# switch-matrix.net
KiCad netlist of a schematic drawn in EAGLE
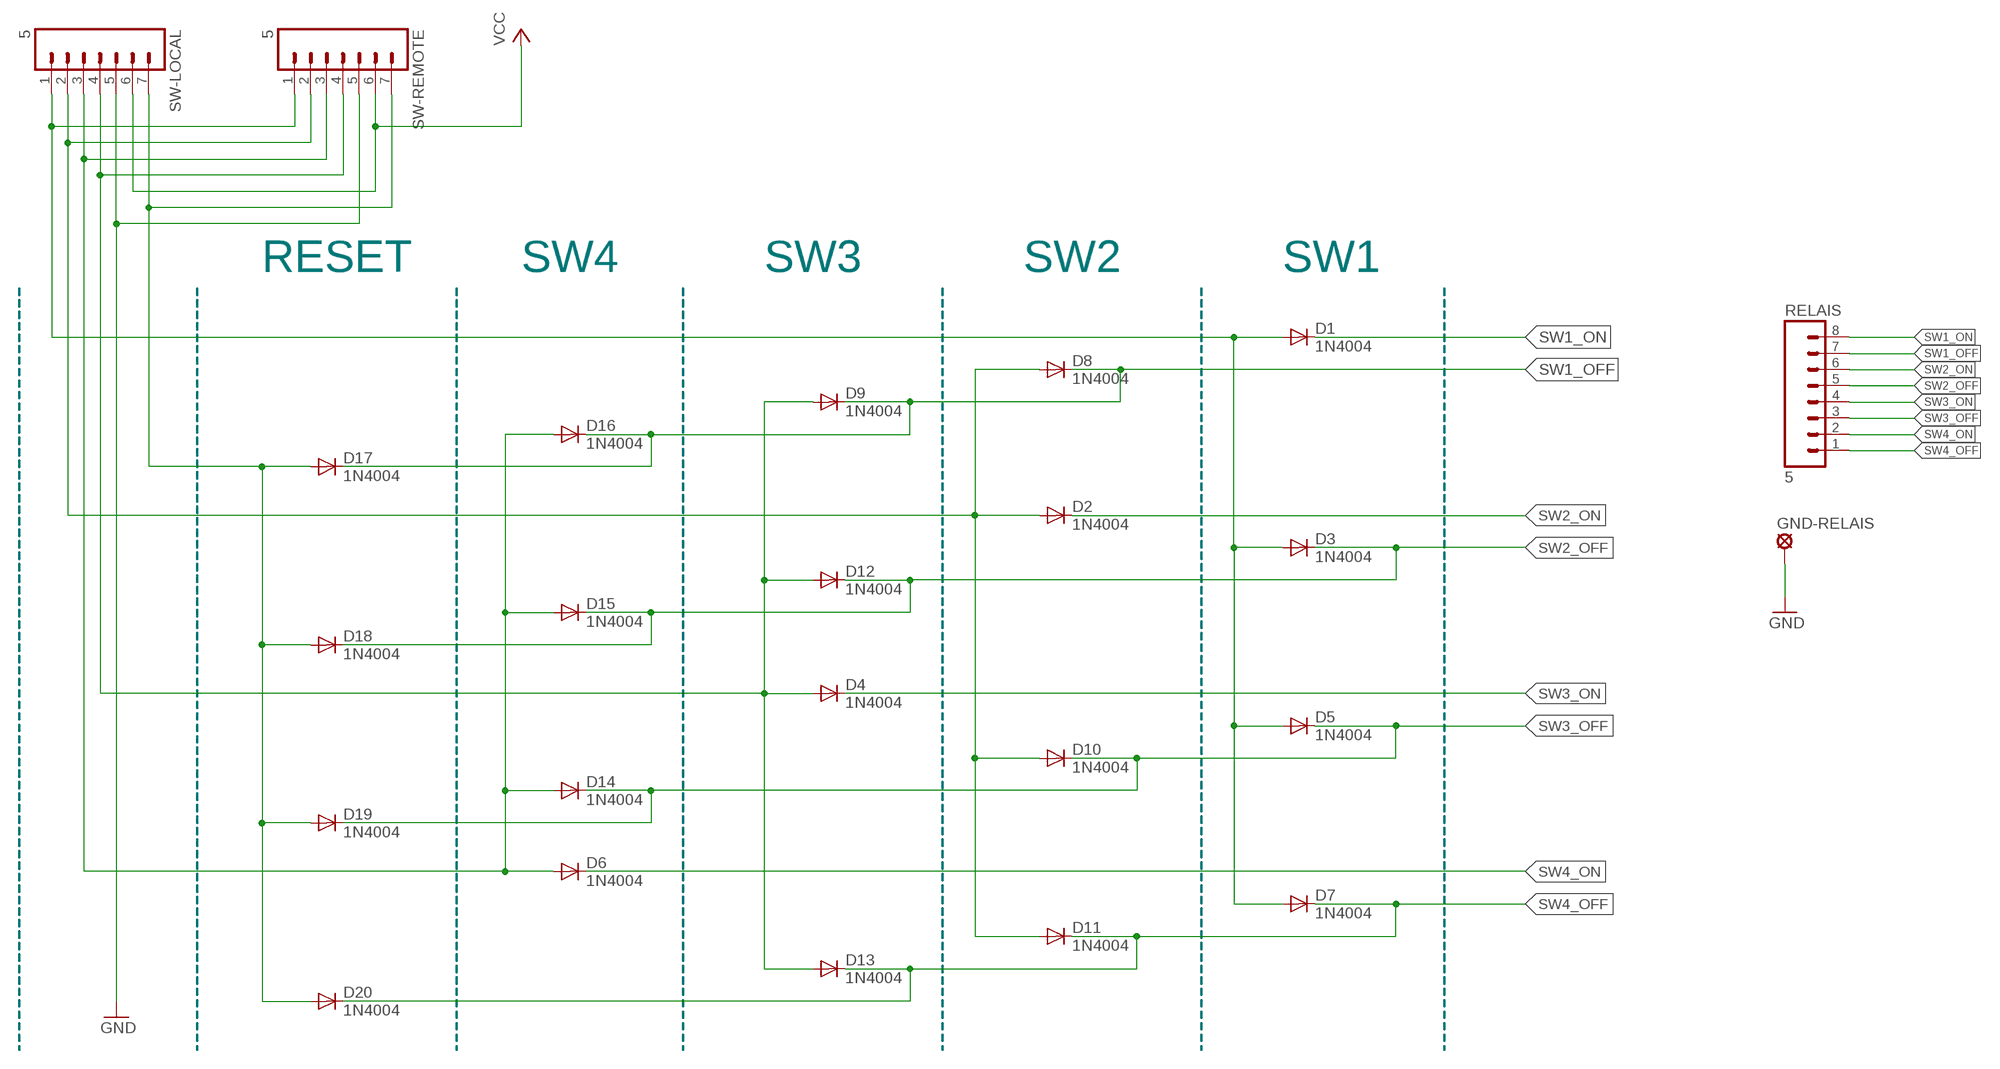
[diagram p0: schematic, sheet 1]

(export (version "E")
  (design (tool "Eeschema 10.0.6"))
  (components
    (comp (ref "D1")
      (value "1N4004")
      (footprint "eagle-import:DO41-10")
      (libsource (lib "eagle-import") (part "1N4004"))
    )
    (comp (ref "D2")
      (value "1N4004")
      (footprint "eagle-import:DO41-10")
      (libsource (lib "eagle-import") (part "1N4004"))
    )
    (comp (ref "D3")
      (value "1N4004")
      (footprint "eagle-import:DO41-10")
      (libsource (lib "eagle-import") (part "1N4004"))
    )
    (comp (ref "D4")
      (value "1N4004")
      (footprint "eagle-import:DO41-10")
      (libsource (lib "eagle-import") (part "1N4004"))
    )
    (comp (ref "D5")
      (value "1N4004")
      (footprint "eagle-import:DO41-10")
      (libsource (lib "eagle-import") (part "1N4004"))
    )
    (comp (ref "D6")
      (value "1N4004")
      (footprint "eagle-import:DO41-10")
      (libsource (lib "eagle-import") (part "1N4004"))
    )
    (comp (ref "D7")
      (value "1N4004")
      (footprint "eagle-import:DO41-10")
      (libsource (lib "eagle-import") (part "1N4004"))
    )
    (comp (ref "D8")
      (value "1N4004")
      (footprint "eagle-import:DO41-10")
      (libsource (lib "eagle-import") (part "1N4004"))
    )
    (comp (ref "D9")
      (value "1N4004")
      (footprint "eagle-import:DO41-10")
      (libsource (lib "eagle-import") (part "1N4004"))
    )
    (comp (ref "D10")
      (value "1N4004")
      (footprint "eagle-import:DO41-10")
      (libsource (lib "eagle-import") (part "1N4004"))
    )
    (comp (ref "D11")
      (value "1N4004")
      (footprint "eagle-import:DO41-10")
      (libsource (lib "eagle-import") (part "1N4004"))
    )
    (comp (ref "D12")
      (value "1N4004")
      (footprint "eagle-import:DO41-10")
      (libsource (lib "eagle-import") (part "1N4004"))
    )
    (comp (ref "D13")
      (value "1N4004")
      (footprint "eagle-import:DO41-10")
      (libsource (lib "eagle-import") (part "1N4004"))
    )
    (comp (ref "D14")
      (value "1N4004")
      (footprint "eagle-import:DO41-10")
      (libsource (lib "eagle-import") (part "1N4004"))
    )
    (comp (ref "D15")
      (value "1N4004")
      (footprint "eagle-import:DO41-10")
      (libsource (lib "eagle-import") (part "1N4004"))
    )
    (comp (ref "D16")
      (value "1N4004")
      (footprint "eagle-import:DO41-10")
      (libsource (lib "eagle-import") (part "1N4004"))
    )
    (comp (ref "D17")
      (value "1N4004")
      (footprint "eagle-import:DO41-10")
      (libsource (lib "eagle-import") (part "1N4004"))
    )
    (comp (ref "D18")
      (value "1N4004")
      (footprint "eagle-import:DO41-10")
      (libsource (lib "eagle-import") (part "1N4004"))
    )
    (comp (ref "D19")
      (value "1N4004")
      (footprint "eagle-import:DO41-10")
      (libsource (lib "eagle-import") (part "1N4004"))
    )
    (comp (ref "D20")
      (value "1N4004")
      (footprint "eagle-import:DO41-10")
      (libsource (lib "eagle-import") (part "1N4004"))
    )
    (comp (ref "GND-RELAIS")
      (value "LSP10")
      (footprint "eagle-import:LSP10")
      (libsource (lib "eagle-import") (part "LSP10"))
    )
    (comp (ref "RELAIS")
      (value "5")
      (footprint "eagle-import:08PA")
      (libsource (lib "eagle-import") (part "MA08"))
    )
    (comp (ref "SW-LOCAL")
      (value "5")
      (footprint "eagle-import:07PA")
      (libsource (lib "eagle-import") (part "MA07"))
    )
    (comp (ref "SW-REMOTE")
      (value "5")
      (footprint "eagle-import:07PA")
      (libsource (lib "eagle-import") (part "MA07"))
    )
  )
  (nets
    (net (code "1") (name "GND") (class "Default")
      (node (ref "GND-RELAIS") (pin "MP") (pinfunction "MP_MP") (pintype "passive"))
      (node (ref "SW-LOCAL") (pin "5") (pinfunction "5_5") (pintype "passive"))
      (node (ref "SW-REMOTE") (pin "5") (pinfunction "5_5") (pintype "passive"))
    )
    (net (code "2") (name "Net-(D1-PadA)") (class "Default")
      (node (ref "D1") (pin "A") (pinfunction "A_A") (pintype "passive"))
      (node (ref "D3") (pin "A") (pinfunction "A_A") (pintype "passive"))
      (node (ref "D5") (pin "A") (pinfunction "A_A") (pintype "passive"))
      (node (ref "D7") (pin "A") (pinfunction "A_A") (pintype "passive"))
      (node (ref "SW-LOCAL") (pin "1") (pinfunction "1_1") (pintype "passive"))
      (node (ref "SW-REMOTE") (pin "1") (pinfunction "1_1") (pintype "passive"))
    )
    (net (code "3") (name "Net-(D10-PadA)") (class "Default")
      (node (ref "D10") (pin "A") (pinfunction "A_A") (pintype "passive"))
      (node (ref "D11") (pin "A") (pinfunction "A_A") (pintype "passive"))
      (node (ref "D2") (pin "A") (pinfunction "A_A") (pintype "passive"))
      (node (ref "D8") (pin "A") (pinfunction "A_A") (pintype "passive"))
      (node (ref "SW-LOCAL") (pin "2") (pinfunction "2_2") (pintype "passive"))
      (node (ref "SW-REMOTE") (pin "2") (pinfunction "2_2") (pintype "passive"))
    )
    (net (code "4") (name "Net-(D12-PadA)") (class "Default")
      (node (ref "D12") (pin "A") (pinfunction "A_A") (pintype "passive"))
      (node (ref "D13") (pin "A") (pinfunction "A_A") (pintype "passive"))
      (node (ref "D4") (pin "A") (pinfunction "A_A") (pintype "passive"))
      (node (ref "D9") (pin "A") (pinfunction "A_A") (pintype "passive"))
      (node (ref "SW-LOCAL") (pin "4") (pinfunction "4_4") (pintype "passive"))
      (node (ref "SW-REMOTE") (pin "4") (pinfunction "4_4") (pintype "passive"))
    )
    (net (code "5") (name "Net-(D14-PadA)") (class "Default")
      (node (ref "D14") (pin "A") (pinfunction "A_A") (pintype "passive"))
      (node (ref "D15") (pin "A") (pinfunction "A_A") (pintype "passive"))
      (node (ref "D16") (pin "A") (pinfunction "A_A") (pintype "passive"))
      (node (ref "D6") (pin "A") (pinfunction "A_A") (pintype "passive"))
      (node (ref "SW-LOCAL") (pin "3") (pinfunction "3_3") (pintype "passive"))
      (node (ref "SW-REMOTE") (pin "3") (pinfunction "3_3") (pintype "passive"))
    )
    (net (code "6") (name "Net-(D17-PadA)") (class "Default")
      (node (ref "D17") (pin "A") (pinfunction "A_A") (pintype "passive"))
      (node (ref "D18") (pin "A") (pinfunction "A_A") (pintype "passive"))
      (node (ref "D19") (pin "A") (pinfunction "A_A") (pintype "passive"))
      (node (ref "D20") (pin "A") (pinfunction "A_A") (pintype "passive"))
      (node (ref "SW-LOCAL") (pin "7") (pinfunction "7_7") (pintype "passive"))
      (node (ref "SW-REMOTE") (pin "7") (pinfunction "7_7") (pintype "passive"))
    )
    (net (code "7") (name "SW1_OFF") (class "Default")
      (node (ref "D16") (pin "C") (pinfunction "C_C") (pintype "passive"))
      (node (ref "D17") (pin "C") (pinfunction "C_C") (pintype "passive"))
      (node (ref "D8") (pin "C") (pinfunction "C_C") (pintype "passive"))
      (node (ref "D9") (pin "C") (pinfunction "C_C") (pintype "passive"))
      (node (ref "RELAIS") (pin "7") (pinfunction "7_7") (pintype "passive"))
    )
    (net (code "8") (name "SW1_ON") (class "Default")
      (node (ref "D1") (pin "C") (pinfunction "C_C") (pintype "passive"))
      (node (ref "RELAIS") (pin "8") (pinfunction "8_8") (pintype "passive"))
    )
    (net (code "9") (name "SW2_OFF") (class "Default")
      (node (ref "D12") (pin "C") (pinfunction "C_C") (pintype "passive"))
      (node (ref "D15") (pin "C") (pinfunction "C_C") (pintype "passive"))
      (node (ref "D18") (pin "C") (pinfunction "C_C") (pintype "passive"))
      (node (ref "D3") (pin "C") (pinfunction "C_C") (pintype "passive"))
      (node (ref "RELAIS") (pin "5") (pinfunction "5_5") (pintype "passive"))
    )
    (net (code "10") (name "SW2_ON") (class "Default")
      (node (ref "D2") (pin "C") (pinfunction "C_C") (pintype "passive"))
      (node (ref "RELAIS") (pin "6") (pinfunction "6_6") (pintype "passive"))
    )
    (net (code "11") (name "SW3_OFF") (class "Default")
      (node (ref "D10") (pin "C") (pinfunction "C_C") (pintype "passive"))
      (node (ref "D14") (pin "C") (pinfunction "C_C") (pintype "passive"))
      (node (ref "D19") (pin "C") (pinfunction "C_C") (pintype "passive"))
      (node (ref "D5") (pin "C") (pinfunction "C_C") (pintype "passive"))
      (node (ref "RELAIS") (pin "3") (pinfunction "3_3") (pintype "passive"))
    )
    (net (code "12") (name "SW3_ON") (class "Default")
      (node (ref "D4") (pin "C") (pinfunction "C_C") (pintype "passive"))
      (node (ref "RELAIS") (pin "4") (pinfunction "4_4") (pintype "passive"))
    )
    (net (code "13") (name "SW4_OFF") (class "Default")
      (node (ref "D11") (pin "C") (pinfunction "C_C") (pintype "passive"))
      (node (ref "D13") (pin "C") (pinfunction "C_C") (pintype "passive"))
      (node (ref "D20") (pin "C") (pinfunction "C_C") (pintype "passive"))
      (node (ref "D7") (pin "C") (pinfunction "C_C") (pintype "passive"))
      (node (ref "RELAIS") (pin "1") (pinfunction "1_1") (pintype "passive"))
    )
    (net (code "14") (name "SW4_ON") (class "Default")
      (node (ref "D6") (pin "C") (pinfunction "C_C") (pintype "passive"))
      (node (ref "RELAIS") (pin "2") (pinfunction "2_2") (pintype "passive"))
    )
    (net (code "15") (name "VCC") (class "Default")
      (node (ref "SW-LOCAL") (pin "6") (pinfunction "6_6") (pintype "passive"))
      (node (ref "SW-REMOTE") (pin "6") (pinfunction "6_6") (pintype "passive"))
    )
  )
)
